# 2d_input.net
KiCad netlist of a schematic drawn in EAGLE
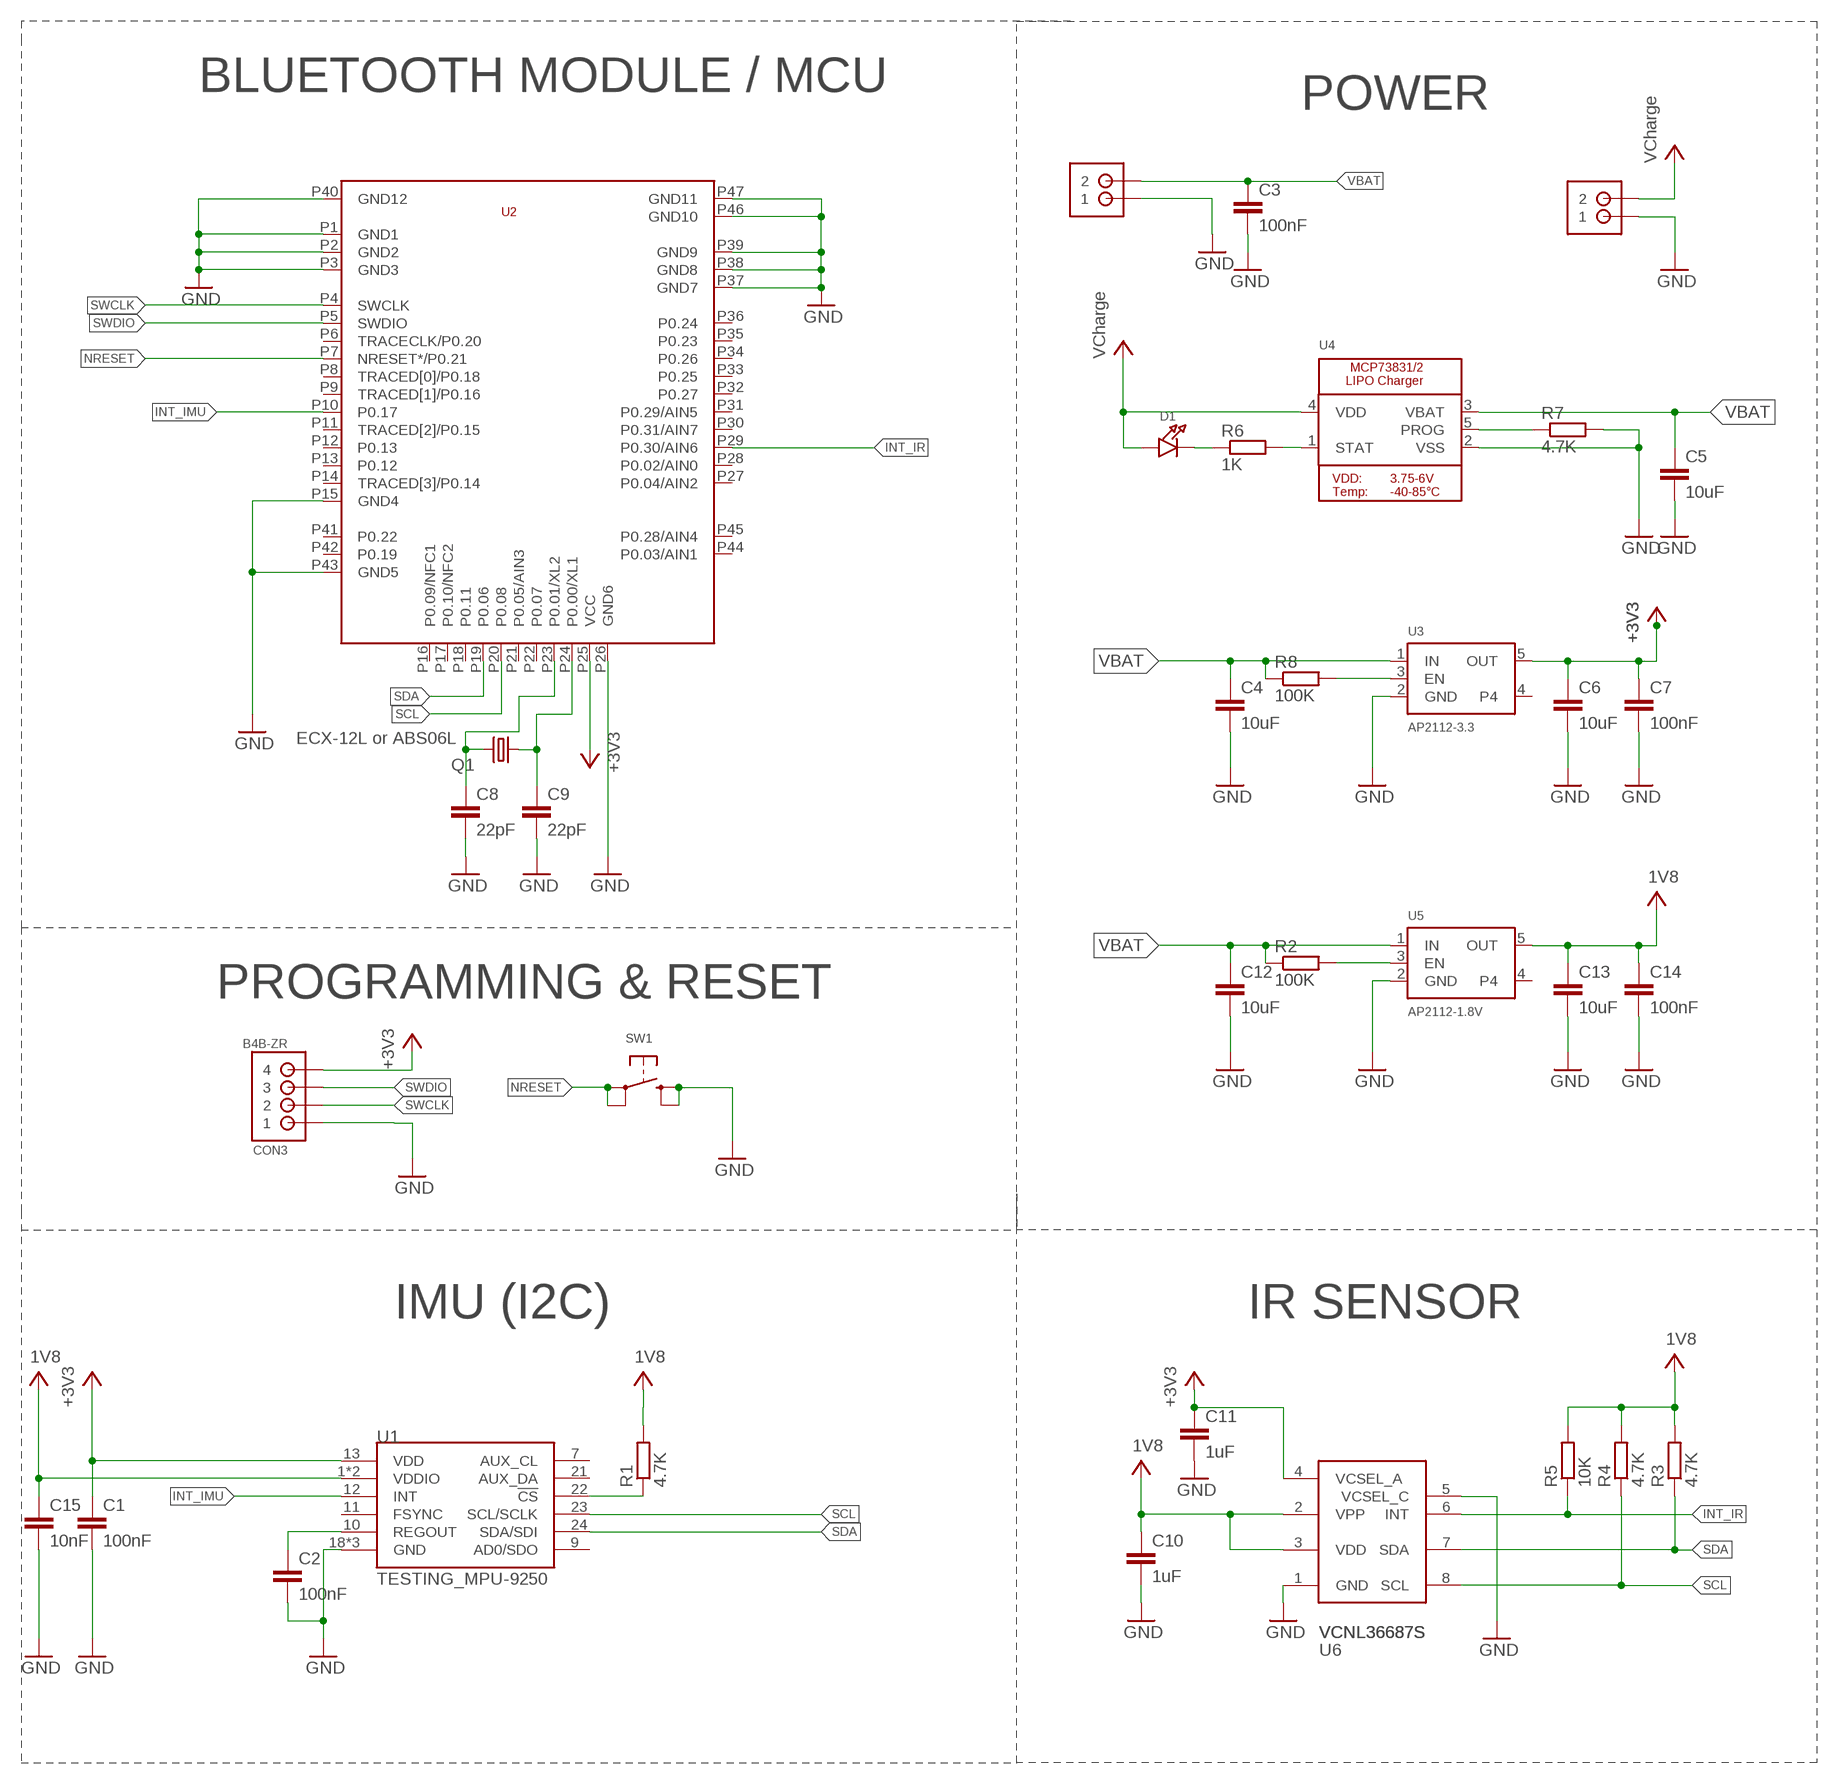
[diagram p0: schematic, sheet 1]

(export (version "E")
  (design (tool "Eeschema 10.0.6"))
  (components
    (comp (ref "C1")
      (value "100nF")
      (footprint "eagle-import:C0402K")
      (libsource (lib "eagle-import") (part "C-EUC0402K"))
    )
    (comp (ref "C2")
      (value "100nF")
      (footprint "eagle-import:C0402K")
      (libsource (lib "eagle-import") (part "C-EUC0402K"))
    )
    (comp (ref "C3")
      (value "100nF")
      (footprint "eagle-import:C0402K")
      (libsource (lib "eagle-import") (part "C-EUC0402K"))
    )
    (comp (ref "C4")
      (value "10uF")
      (footprint "eagle-import:C0402K")
      (libsource (lib "eagle-import") (part "C-EUC0402K"))
    )
    (comp (ref "C5")
      (value "10uF")
      (footprint "eagle-import:C0402K")
      (libsource (lib "eagle-import") (part "C-EUC0402K"))
    )
    (comp (ref "C6")
      (value "10uF")
      (footprint "eagle-import:C0402K")
      (libsource (lib "eagle-import") (part "C-EUC0402K"))
    )
    (comp (ref "C7")
      (value "100nF")
      (footprint "eagle-import:C0402K")
      (libsource (lib "eagle-import") (part "C-EUC0402K"))
    )
    (comp (ref "C8")
      (value "22pF")
      (footprint "eagle-import:C0402K")
      (libsource (lib "eagle-import") (part "C-EUC0402K"))
    )
    (comp (ref "C9")
      (value "22pF")
      (footprint "eagle-import:C0402K")
      (libsource (lib "eagle-import") (part "C-EUC0402K"))
    )
    (comp (ref "C10")
      (value "1uF")
      (footprint "eagle-import:C0402K")
      (libsource (lib "eagle-import") (part "C-EUC0402K"))
    )
    (comp (ref "C11")
      (value "1uF")
      (footprint "eagle-import:C0402K")
      (libsource (lib "eagle-import") (part "C-EUC0402K"))
    )
    (comp (ref "C12")
      (value "10uF")
      (footprint "eagle-import:C0402K")
      (libsource (lib "eagle-import") (part "C-EUC0402K"))
    )
    (comp (ref "C13")
      (value "10uF")
      (footprint "eagle-import:C0402K")
      (libsource (lib "eagle-import") (part "C-EUC0402K"))
    )
    (comp (ref "C14")
      (value "100nF")
      (footprint "eagle-import:C0402K")
      (libsource (lib "eagle-import") (part "C-EUC0402K"))
    )
    (comp (ref "C15")
      (value "10nF")
      (footprint "eagle-import:C0402K")
      (libsource (lib "eagle-import") (part "C-EUC0402K"))
    )
    (comp (ref "CON1")
      (value "B2B-ZR")
      (footprint "eagle-import:B2B-ZR")
      (libsource (lib "eagle-import") (part "B2B-ZR"))
    )
    (comp (ref "CON2")
      (value "B2B-ZR")
      (footprint "eagle-import:B2B-ZR")
      (libsource (lib "eagle-import") (part "B2B-ZR"))
    )
    (comp (ref "CON3")
      (value "B4B-ZR")
      (footprint "eagle-import:B4B-ZR")
      (libsource (lib "eagle-import") (part "B4B-ZR"))
    )
    (comp (ref "D1")
      (value "MICROBUILDER_LED0603_NOOUTLINE")
      (footprint "eagle-import:MICROBUILDER_CHIPLED_0603_NOOUTLINE")
      (libsource (lib "eagle-import") (part "MICROBUILDER_LED0603_NOOUTLINE"))
    )
    (comp (ref "Q1")
      (value "ECX-12L or ABS06L")
      (footprint "eagle-import:2.0X1.2")
      (libsource (lib "eagle-import") (part "KX-327-RT"))
    )
    (comp (ref "R1")
      (value "4.7K")
      (footprint "eagle-import:R0402")
      (libsource (lib "eagle-import") (part "R-EU_R0402"))
    )
    (comp (ref "R2")
      (value "100K")
      (footprint "eagle-import:R0402")
      (libsource (lib "eagle-import") (part "R-EU_R0402"))
    )
    (comp (ref "R3")
      (value "4.7K")
      (footprint "eagle-import:R0402")
      (libsource (lib "eagle-import") (part "R-EU_R0402"))
    )
    (comp (ref "R4")
      (value "4.7K")
      (footprint "eagle-import:R0402")
      (libsource (lib "eagle-import") (part "R-EU_R0402"))
    )
    (comp (ref "R5")
      (value "10K")
      (footprint "eagle-import:R0402")
      (libsource (lib "eagle-import") (part "R-EU_R0402"))
    )
    (comp (ref "R6")
      (value "1K")
      (footprint "eagle-import:R0402")
      (libsource (lib "eagle-import") (part "R-EU_R0402"))
    )
    (comp (ref "R7")
      (value "4.7K")
      (footprint "eagle-import:R0402")
      (libsource (lib "eagle-import") (part "R-EU_R0402"))
    )
    (comp (ref "R8")
      (value "100K")
      (footprint "eagle-import:R0402")
      (libsource (lib "eagle-import") (part "R-EU_R0402"))
    )
    (comp (ref "SW1")
      (value "MICROBUILDER_SWITCH_TACT_SMT4.6X2.8")
      (footprint "eagle-import:MICROBUILDER_BTN_KMR2_4.6X2.8")
      (libsource (lib "eagle-import") (part "MICROBUILDER_SWITCH_TACT_SMT4.6X2.8"))
    )
    (comp (ref "U1")
      (value "TESTING_MPU-9250")
      (footprint "eagle-import:TESTING_QFN24_PAD")
      (libsource (lib "eagle-import") (part "TESTING_MPU-9250"))
    )
    (comp (ref "U2")
      (value "BMD-350")
      (footprint "eagle-import:BMD-350")
      (libsource (lib "eagle-import") (part "BMD-350"))
    )
    (comp (ref "U3")
      (value "AP2112-3.3")
      (footprint "eagle-import:MICROBUILDER_SOT23-5")
      (libsource (lib "eagle-import") (part "MICROBUILDER_VREG_SOT23-5"))
    )
    (comp (ref "U4")
      (value "MICROBUILDER_MCP73831/2")
      (footprint "eagle-import:MICROBUILDER_SOT23-5")
      (libsource (lib "eagle-import") (part "MICROBUILDER_MCP73831/2"))
    )
    (comp (ref "U5")
      (value "AP2112-1.8V")
      (footprint "eagle-import:MICROBUILDER_SOT23-5")
      (libsource (lib "eagle-import") (part "MICROBUILDER_VREG_SOT23-5"))
    )
    (comp (ref "U6")
      (value "VCNL36687S")
      (footprint "eagle-import:VCNL36687S")
      (libsource (lib "eagle-import") (part "VCNL36687S"))
    )
  )
  (nets
    (net (code "1") (name "+3V3") (class "Default")
      (node (ref "C1") (pin "1") (pinfunction "1_1") (pintype "passive"))
      (node (ref "C11") (pin "1") (pinfunction "1_1") (pintype "passive"))
      (node (ref "C6") (pin "1") (pinfunction "1_1") (pintype "passive"))
      (node (ref "C7") (pin "1") (pinfunction "1_1") (pintype "passive"))
      (node (ref "CON3") (pin "4") (pinfunction "4_4") (pintype "bidirectional"))
      (node (ref "U1") (pin "13") (pinfunction "VDD_13") (pintype "bidirectional"))
      (node (ref "U2") (pin "P25") (pinfunction "VCC_P25") (pintype "bidirectional"))
      (node (ref "U3") (pin "5") (pinfunction "OUT_5") (pintype "power_in"))
      (node (ref "U6") (pin "4") (pinfunction "VCSEL_A_4") (pintype "bidirectional"))
    )
    (net (code "2") (name "1V8") (class "Default")
      (node (ref "C10") (pin "1") (pinfunction "1_1") (pintype "passive"))
      (node (ref "C13") (pin "1") (pinfunction "1_1") (pintype "passive"))
      (node (ref "C14") (pin "1") (pinfunction "1_1") (pintype "passive"))
      (node (ref "C15") (pin "1") (pinfunction "1_1") (pintype "passive"))
      (node (ref "R1") (pin "2") (pinfunction "2_2") (pintype "passive"))
      (node (ref "R3") (pin "2") (pinfunction "2_2") (pintype "passive"))
      (node (ref "R4") (pin "2") (pinfunction "2_2") (pintype "passive"))
      (node (ref "R5") (pin "2") (pinfunction "2_2") (pintype "passive"))
      (node (ref "U1") (pin "1") (pinfunction "VDDIO_1") (pintype "bidirectional"))
      (node (ref "U1") (pin "8") (pinfunction "VDDIO_8") (pintype "bidirectional"))
      (node (ref "U5") (pin "5") (pinfunction "OUT_5") (pintype "power_in"))
      (node (ref "U6") (pin "2") (pinfunction "VPP_2") (pintype "bidirectional"))
      (node (ref "U6") (pin "3") (pinfunction "VDD_3") (pintype "bidirectional"))
    )
    (net (code "3") (name "GND") (class "Default")
      (node (ref "C1") (pin "2") (pinfunction "2_2") (pintype "passive"))
      (node (ref "C10") (pin "2") (pinfunction "2_2") (pintype "passive"))
      (node (ref "C11") (pin "2") (pinfunction "2_2") (pintype "passive"))
      (node (ref "C12") (pin "2") (pinfunction "2_2") (pintype "passive"))
      (node (ref "C13") (pin "2") (pinfunction "2_2") (pintype "passive"))
      (node (ref "C14") (pin "2") (pinfunction "2_2") (pintype "passive"))
      (node (ref "C15") (pin "2") (pinfunction "2_2") (pintype "passive"))
      (node (ref "C2") (pin "2") (pinfunction "2_2") (pintype "passive"))
      (node (ref "C3") (pin "2") (pinfunction "2_2") (pintype "passive"))
      (node (ref "C4") (pin "2") (pinfunction "2_2") (pintype "passive"))
      (node (ref "C5") (pin "2") (pinfunction "2_2") (pintype "passive"))
      (node (ref "C6") (pin "2") (pinfunction "2_2") (pintype "passive"))
      (node (ref "C7") (pin "2") (pinfunction "2_2") (pintype "passive"))
      (node (ref "C8") (pin "2") (pinfunction "2_2") (pintype "passive"))
      (node (ref "C9") (pin "2") (pinfunction "2_2") (pintype "passive"))
      (node (ref "CON1") (pin "1") (pinfunction "1_1") (pintype "bidirectional"))
      (node (ref "CON2") (pin "1") (pinfunction "1_1") (pintype "bidirectional"))
      (node (ref "CON3") (pin "1") (pinfunction "1_1") (pintype "bidirectional"))
      (node (ref "R7") (pin "2") (pinfunction "2_2") (pintype "passive"))
      (node (ref "SW1") (pin "B") (pinfunction "S_B") (pintype "passive"))
      (node (ref "SW1") (pin "B'") (pinfunction "S1_B'") (pintype "passive"))
      (node (ref "U1") (pin "18") (pinfunction "GND_18") (pintype "bidirectional"))
      (node (ref "U1") (pin "20") (pinfunction "GND_20") (pintype "bidirectional"))
      (node (ref "U1") (pin "CENTER") (pinfunction "GND_CENTER") (pintype "bidirectional"))
      (node (ref "U2") (pin "P1") (pinfunction "GND1_P1") (pintype "bidirectional"))
      (node (ref "U2") (pin "P15") (pinfunction "GND4_P15") (pintype "bidirectional"))
      (node (ref "U2") (pin "P2") (pinfunction "GND2_P2") (pintype "bidirectional"))
      (node (ref "U2") (pin "P26") (pinfunction "GND6_P26") (pintype "bidirectional"))
      (node (ref "U2") (pin "P3") (pinfunction "GND3_P3") (pintype "bidirectional"))
      (node (ref "U2") (pin "P37") (pinfunction "GND7_P37") (pintype "bidirectional"))
      (node (ref "U2") (pin "P38") (pinfunction "GND8_P38") (pintype "bidirectional"))
      (node (ref "U2") (pin "P39") (pinfunction "GND9_P39") (pintype "bidirectional"))
      (node (ref "U2") (pin "P40") (pinfunction "GND12_P40") (pintype "bidirectional"))
      (node (ref "U2") (pin "P43") (pinfunction "GND5_P43") (pintype "bidirectional"))
      (node (ref "U2") (pin "P46") (pinfunction "GND10_P46") (pintype "bidirectional"))
      (node (ref "U2") (pin "P47") (pinfunction "GND11_P47") (pintype "bidirectional"))
      (node (ref "U3") (pin "2") (pinfunction "GND_2") (pintype "power_in"))
      (node (ref "U4") (pin "2") (pinfunction "VSS_2") (pintype "power_in"))
      (node (ref "U5") (pin "2") (pinfunction "GND_2") (pintype "power_in"))
      (node (ref "U6") (pin "1") (pinfunction "GND_1") (pintype "bidirectional"))
      (node (ref "U6") (pin "5") (pinfunction "VCSEL_C_5") (pintype "bidirectional"))
    )
    (net (code "4") (name "INT_IMU") (class "Default")
      (node (ref "U1") (pin "12") (pinfunction "INT_12") (pintype "bidirectional"))
      (node (ref "U2") (pin "P10") (pinfunction "P0.17_P10") (pintype "bidirectional"))
    )
    (net (code "5") (name "INT_IR") (class "Default")
      (node (ref "R5") (pin "1") (pinfunction "1_1") (pintype "passive"))
      (node (ref "U2") (pin "P29") (pinfunction "P0.30/AIN6_P29") (pintype "bidirectional"))
      (node (ref "U6") (pin "6") (pinfunction "INT_6") (pintype "bidirectional"))
    )
    (net (code "6") (name "NRESET") (class "Default")
      (node (ref "SW1") (pin "A") (pinfunction "P_A") (pintype "passive"))
      (node (ref "SW1") (pin "A'") (pinfunction "P1_A'") (pintype "passive"))
      (node (ref "U2") (pin "P7") (pinfunction "NRESET*/P0.21_P7") (pintype "bidirectional"))
    )
    (net (code "7") (name "Net-(D1-PadC)") (class "Default")
      (node (ref "D1") (pin "C") (pinfunction "C_C") (pintype "passive"))
      (node (ref "R6") (pin "1") (pinfunction "1_1") (pintype "passive"))
    )
    (net (code "8") (name "Net-(U1-REGOUT)") (class "Default")
      (node (ref "C2") (pin "1") (pinfunction "1_1") (pintype "passive"))
      (node (ref "U1") (pin "10") (pinfunction "REGOUT_10") (pintype "bidirectional"))
    )
    (net (code "9") (name "Net-(U1-~{CS})") (class "Default")
      (node (ref "R1") (pin "1") (pinfunction "1_1") (pintype "passive"))
      (node (ref "U1") (pin "22") (pinfunction "~{CS}_22") (pintype "bidirectional"))
    )
    (net (code "10") (name "Net-(U2-P0.00{slash}XL1)") (class "Default")
      (node (ref "C9") (pin "1") (pinfunction "1_1") (pintype "passive"))
      (node (ref "Q1") (pin "1") (pinfunction "1_1") (pintype "passive"))
      (node (ref "U2") (pin "P24") (pinfunction "P0.00/XL1_P24") (pintype "bidirectional"))
    )
    (net (code "11") (name "Net-(U2-P0.01{slash}XL2)") (class "Default")
      (node (ref "C8") (pin "1") (pinfunction "1_1") (pintype "passive"))
      (node (ref "Q1") (pin "2") (pinfunction "2_2") (pintype "passive"))
      (node (ref "U2") (pin "P23") (pinfunction "P0.01/XL2_P23") (pintype "bidirectional"))
    )
    (net (code "12") (name "Net-(U3-EN)") (class "Default")
      (node (ref "R8") (pin "2") (pinfunction "2_2") (pintype "passive"))
      (node (ref "U3") (pin "3") (pinfunction "EN_3") (pintype "input"))
    )
    (net (code "13") (name "Net-(U4-PROG)") (class "Default")
      (node (ref "R7") (pin "1") (pinfunction "1_1") (pintype "passive"))
      (node (ref "U4") (pin "5") (pinfunction "PROG_5") (pintype "input"))
    )
    (net (code "14") (name "Net-(U4-STAT)") (class "Default")
      (node (ref "R6") (pin "2") (pinfunction "2_2") (pintype "passive"))
      (node (ref "U4") (pin "1") (pinfunction "STAT_1") (pintype "output"))
    )
    (net (code "15") (name "Net-(U5-EN)") (class "Default")
      (node (ref "R2") (pin "2") (pinfunction "2_2") (pintype "passive"))
      (node (ref "U5") (pin "3") (pinfunction "EN_3") (pintype "input"))
    )
    (net (code "16") (name "SCL") (class "Default")
      (node (ref "R4") (pin "1") (pinfunction "1_1") (pintype "passive"))
      (node (ref "U1") (pin "23") (pinfunction "SCL/SCLK_23") (pintype "bidirectional"))
      (node (ref "U2") (pin "P20") (pinfunction "P0.08_P20") (pintype "bidirectional"))
      (node (ref "U6") (pin "8") (pinfunction "SCL_8") (pintype "bidirectional"))
    )
    (net (code "17") (name "SDA") (class "Default")
      (node (ref "R3") (pin "1") (pinfunction "1_1") (pintype "passive"))
      (node (ref "U1") (pin "24") (pinfunction "SDA/SDI_24") (pintype "bidirectional"))
      (node (ref "U2") (pin "P19") (pinfunction "P0.06_P19") (pintype "bidirectional"))
      (node (ref "U6") (pin "7") (pinfunction "SDA_7") (pintype "bidirectional"))
    )
    (net (code "18") (name "SWCLK") (class "Default")
      (node (ref "CON3") (pin "2") (pinfunction "2_2") (pintype "bidirectional"))
      (node (ref "U2") (pin "P4") (pinfunction "SWCLK_P4") (pintype "bidirectional"))
    )
    (net (code "19") (name "SWDIO") (class "Default")
      (node (ref "CON3") (pin "3") (pinfunction "3_3") (pintype "bidirectional"))
      (node (ref "U2") (pin "P5") (pinfunction "SWDIO_P5") (pintype "bidirectional"))
    )
    (net (code "20") (name "VBAT") (class "Default")
      (node (ref "C12") (pin "1") (pinfunction "1_1") (pintype "passive"))
      (node (ref "C3") (pin "1") (pinfunction "1_1") (pintype "passive"))
      (node (ref "C4") (pin "1") (pinfunction "1_1") (pintype "passive"))
      (node (ref "C5") (pin "1") (pinfunction "1_1") (pintype "passive"))
      (node (ref "CON1") (pin "2") (pinfunction "2_2") (pintype "bidirectional"))
      (node (ref "R2") (pin "1") (pinfunction "1_1") (pintype "passive"))
      (node (ref "R8") (pin "1") (pinfunction "1_1") (pintype "passive"))
      (node (ref "U3") (pin "1") (pinfunction "IN_1") (pintype "power_in"))
      (node (ref "U4") (pin "3") (pinfunction "VBAT_3") (pintype "power_in"))
      (node (ref "U5") (pin "1") (pinfunction "IN_1") (pintype "power_in"))
    )
    (net (code "21") (name "VCharge") (class "Default")
      (node (ref "CON2") (pin "2") (pinfunction "2_2") (pintype "bidirectional"))
      (node (ref "D1") (pin "A") (pinfunction "A_A") (pintype "passive"))
      (node (ref "U4") (pin "4") (pinfunction "VDD_4") (pintype "power_in"))
    )
    (net (code "22") (name "unconnected-(U1-AD0{slash}SDO-Pad9)") (class "Default")
      (node (ref "U1") (pin "9") (pinfunction "AD0/SDO_9") (pintype "bidirectional"))
    )
    (net (code "23") (name "unconnected-(U1-AUX_CL-Pad7)") (class "Default")
      (node (ref "U1") (pin "7") (pinfunction "AUX_CL_7") (pintype "bidirectional"))
    )
    (net (code "24") (name "unconnected-(U1-AUX_DA-Pad21)") (class "Default")
      (node (ref "U1") (pin "21") (pinfunction "AUX_DA_21") (pintype "bidirectional"))
    )
    (net (code "25") (name "unconnected-(U1-FSYNC-Pad11)") (class "Default")
      (node (ref "U1") (pin "11") (pinfunction "FSYNC_11") (pintype "bidirectional"))
    )
    (net (code "26") (name "unconnected-(U2-P0.02{slash}AIN0-PadP28)") (class "Default")
      (node (ref "U2") (pin "P28") (pinfunction "P0.02/AIN0_P28") (pintype "bidirectional"))
    )
    (net (code "27") (name "unconnected-(U2-P0.03{slash}AIN1-PadP44)") (class "Default")
      (node (ref "U2") (pin "P44") (pinfunction "P0.03/AIN1_P44") (pintype "bidirectional"))
    )
    (net (code "28") (name "unconnected-(U2-P0.04{slash}AIN2-PadP27)") (class "Default")
      (node (ref "U2") (pin "P27") (pinfunction "P0.04/AIN2_P27") (pintype "bidirectional"))
    )
    (net (code "29") (name "unconnected-(U2-P0.05{slash}AIN3-PadP21)") (class "Default")
      (node (ref "U2") (pin "P21") (pinfunction "P0.05/AIN3_P21") (pintype "bidirectional"))
    )
    (net (code "30") (name "unconnected-(U2-P0.07-PadP22)") (class "Default")
      (node (ref "U2") (pin "P22") (pinfunction "P0.07_P22") (pintype "bidirectional"))
    )
    (net (code "31") (name "unconnected-(U2-P0.09{slash}NFC1-PadP16)") (class "Default")
      (node (ref "U2") (pin "P16") (pinfunction "P0.09/NFC1_P16") (pintype "bidirectional"))
    )
    (net (code "32") (name "unconnected-(U2-P0.10{slash}NFC2-PadP17)") (class "Default")
      (node (ref "U2") (pin "P17") (pinfunction "P0.10/NFC2_P17") (pintype "bidirectional"))
    )
    (net (code "33") (name "unconnected-(U2-P0.11-PadP18)") (class "Default")
      (node (ref "U2") (pin "P18") (pinfunction "P0.11_P18") (pintype "bidirectional"))
    )
    (net (code "34") (name "unconnected-(U2-P0.12-PadP13)") (class "Default")
      (node (ref "U2") (pin "P13") (pinfunction "P0.12_P13") (pintype "bidirectional"))
    )
    (net (code "35") (name "unconnected-(U2-P0.13-PadP12)") (class "Default")
      (node (ref "U2") (pin "P12") (pinfunction "P0.13_P12") (pintype "bidirectional"))
    )
    (net (code "36") (name "unconnected-(U2-P0.19-PadP42)") (class "Default")
      (node (ref "U2") (pin "P42") (pinfunction "P0.19_P42") (pintype "bidirectional"))
    )
    (net (code "37") (name "unconnected-(U2-P0.22-PadP41)") (class "Default")
      (node (ref "U2") (pin "P41") (pinfunction "P0.22_P41") (pintype "bidirectional"))
    )
    (net (code "38") (name "unconnected-(U2-P0.23-PadP35)") (class "Default")
      (node (ref "U2") (pin "P35") (pinfunction "P0.23_P35") (pintype "bidirectional"))
    )
    (net (code "39") (name "unconnected-(U2-P0.24-PadP36)") (class "Default")
      (node (ref "U2") (pin "P36") (pinfunction "P0.24_P36") (pintype "bidirectional"))
    )
    (net (code "40") (name "unconnected-(U2-P0.25-PadP33)") (class "Default")
      (node (ref "U2") (pin "P33") (pinfunction "P0.25_P33") (pintype "bidirectional"))
    )
    (net (code "41") (name "unconnected-(U2-P0.26-PadP34)") (class "Default")
      (node (ref "U2") (pin "P34") (pinfunction "P0.26_P34") (pintype "bidirectional"))
    )
    (net (code "42") (name "unconnected-(U2-P0.27-PadP32)") (class "Default")
      (node (ref "U2") (pin "P32") (pinfunction "P0.27_P32") (pintype "bidirectional"))
    )
    (net (code "43") (name "unconnected-(U2-P0.28{slash}AIN4-PadP45)") (class "Default")
      (node (ref "U2") (pin "P45") (pinfunction "P0.28/AIN4_P45") (pintype "bidirectional"))
    )
    (net (code "44") (name "unconnected-(U2-P0.29{slash}AIN5-PadP31)") (class "Default")
      (node (ref "U2") (pin "P31") (pinfunction "P0.29/AIN5_P31") (pintype "bidirectional"))
    )
    (net (code "45") (name "unconnected-(U2-P0.31{slash}AIN7-PadP30)") (class "Default")
      (node (ref "U2") (pin "P30") (pinfunction "P0.31/AIN7_P30") (pintype "bidirectional"))
    )
    (net (code "46") (name "unconnected-(U2-TRACECLK{slash}P0.20-PadP6)") (class "Default")
      (node (ref "U2") (pin "P6") (pinfunction "TRACECLK/P0.20_P6") (pintype "bidirectional"))
    )
    (net (code "47") (name "unconnected-(U2-TRACED[0]{slash}P0.18-PadP8)") (class "Default")
      (node (ref "U2") (pin "P8") (pinfunction "TRACED[0]/P0.18_P8") (pintype "bidirectional"))
    )
    (net (code "48") (name "unconnected-(U2-TRACED[1]{slash}P0.16-PadP9)") (class "Default")
      (node (ref "U2") (pin "P9") (pinfunction "TRACED[1]/P0.16_P9") (pintype "bidirectional"))
    )
    (net (code "49") (name "unconnected-(U2-TRACED[2]{slash}P0.15-PadP11)") (class "Default")
      (node (ref "U2") (pin "P11") (pinfunction "TRACED[2]/P0.15_P11") (pintype "bidirectional"))
    )
    (net (code "50") (name "unconnected-(U2-TRACED[3]{slash}P0.14-PadP14)") (class "Default")
      (node (ref "U2") (pin "P14") (pinfunction "TRACED[3]/P0.14_P14") (pintype "bidirectional"))
    )
    (net (code "51") (name "unconnected-(U3-P4-Pad4)") (class "Default")
      (node (ref "U3") (pin "4") (pinfunction "P4_4") (pintype "bidirectional"))
    )
    (net (code "52") (name "unconnected-(U5-P4-Pad4)") (class "Default")
      (node (ref "U5") (pin "4") (pinfunction "P4_4") (pintype "bidirectional"))
    )
  )
)
